# DIO_buffer.net
KiCad netlist of a schematic drawn in Altium Designer
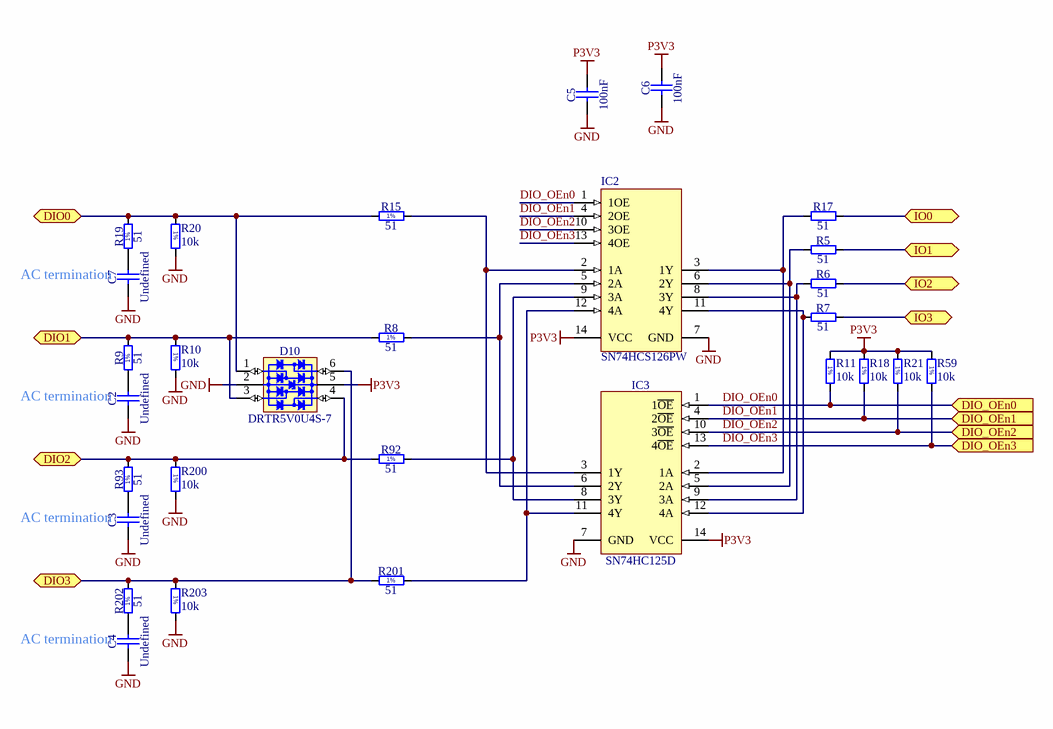
[diagram p0: DIO_buffer.schdoc]

(export (version "E")
  (design (tool "Eeschema 10.0.6"))
  (components
    (comp (ref "C2")
      (value "Undefined")
      (footprint "CAPC1608X90N")
      (description "Non-polarised capacitor")
      (fields (field (name "PART NUMBER") "CC0603_NO-VALUE") (field (name "AUTHOR") "CERN DEM MR"))
      (libsource (lib "Capacitors") (part "Capacitor - non polarized"))
    )
    (comp (ref "C3")
      (value "Undefined")
      (footprint "CAPC1608X90N")
      (description "Non-polarised capacitor")
      (fields (field (name "PART NUMBER") "CC0603_NO-VALUE") (field (name "AUTHOR") "CERN DEM MR"))
      (libsource (lib "Capacitors") (part "Capacitor - non polarized"))
    )
    (comp (ref "C4")
      (value "Undefined")
      (footprint "CAPC1608X90N")
      (description "Non-polarised capacitor")
      (fields (field (name "PART NUMBER") "CC0603_NO-VALUE") (field (name "AUTHOR") "CERN DEM MR"))
      (libsource (lib "Capacitors") (part "Capacitor - non polarized"))
    )
    (comp (ref "C5")
      (value "100nF")
      (footprint "CAPC1005X55N")
      (description "Non-polarised capacitor")
      (fields
        (field (name "PART NUMBER") "CC0402_100NF_16V_10%_X5R")
        (field (name "VOLTAGE") "16V")
        (field (name "AUTHOR") "CERN DEM JLC")
      )
      (libsource (lib "Capacitors") (part "Capacitor - non polarized"))
    )
    (comp (ref "C6")
      (value "100nF")
      (footprint "CAPC1005X55N")
      (description "Non-polarised capacitor")
      (fields
        (field (name "PART NUMBER") "CC0402_100NF_16V_10%_X5R")
        (field (name "VOLTAGE") "16V")
        (field (name "AUTHOR") "CERN DEM JLC")
      )
      (libsource (lib "Capacitors") (part "Capacitor - non polarized"))
    )
    (comp (ref "C7")
      (value "Undefined")
      (footprint "CAPC1608X90N")
      (description "Non-polarised capacitor")
      (fields (field (name "PART NUMBER") "CC0603_NO-VALUE") (field (name "AUTHOR") "CERN DEM MR"))
      (libsource (lib "Capacitors") (part "Capacitor - non polarized"))
    )
    (comp (ref "D10")
      (value "DRTR5V0U4S-7")
      (footprint "SOT65P210X110-6N")
      (description "Integrated Quad Ultra-Low Capacitance ESD Protection")
      (fields (field (name "MANUFACTURER") "DIODES") (field (name "AUTHOR") "GK"))
      (libsource (lib "Diodes") (part "D_TVS_DRTR5V0U4S-7"))
    )
    (comp (ref "IC2")
      (value "SN74HCS126PW")
      (footprint "SOP65P640X120-14N")
      (description "Quadruple Bus Buffer with 3-State Outputs")
      (fields (field (name "MANUFACTURER") "TEXAS INSTRUMENTS") (field (name "AUTHOR") "CERN DEM BC"))
      (libsource (lib "ICs And Semiconductors") (part "74126"))
    )
    (comp (ref "IC3")
      (value "SN74HC125D")
      (footprint "SOIC127P600X175-14N")
      (description "Quadruple Bus Buffer with 3-State Outputs")
      (fields (field (name "MANUFACTURER") "TEXAS INSTRUMENTS") (field (name "AUTHOR") "CERN DEM JLC"))
      (libsource (lib "ICs And Semiconductors") (part "74125"))
    )
    (comp (ref "R5")
      (value "51")
      (footprint "RESC1005X40N")
      (description "Resistor - 1%")
      (fields
        (field (name "PART NUMBER") "R0402_51R_1%_0.0625W_100PPM")
        (field (name "POWER") "0.0625W")
        (field (name "AUTHOR") "CERN DEM JLC")
      )
      (libsource (lib "Resistors") (part "Resistor - 1%"))
    )
    (comp (ref "R6")
      (value "51")
      (footprint "RESC1005X40N")
      (description "Resistor - 1%")
      (fields
        (field (name "PART NUMBER") "R0402_51R_1%_0.0625W_100PPM")
        (field (name "POWER") "0.0625W")
        (field (name "AUTHOR") "CERN DEM JLC")
      )
      (libsource (lib "Resistors") (part "Resistor - 1%"))
    )
    (comp (ref "R7")
      (value "51")
      (footprint "RESC1005X40N")
      (description "Resistor - 1%")
      (fields
        (field (name "PART NUMBER") "R0402_51R_1%_0.0625W_100PPM")
        (field (name "POWER") "0.0625W")
        (field (name "AUTHOR") "CERN DEM JLC")
      )
      (libsource (lib "Resistors") (part "Resistor - 1%"))
    )
    (comp (ref "R8")
      (value "51")
      (footprint "RESC1005X40N")
      (description "Resistor - 1%")
      (fields
        (field (name "PART NUMBER") "R0402_51R_1%_0.0625W_100PPM")
        (field (name "POWER") "0.0625W")
        (field (name "AUTHOR") "CERN DEM JLC")
      )
      (libsource (lib "Resistors") (part "Resistor - 1%"))
    )
    (comp (ref "R9")
      (value "51")
      (footprint "RESC1005X40N")
      (description "Resistor - 1%")
      (fields
        (field (name "PART NUMBER") "R0402_51R_1%_0.0625W_100PPM")
        (field (name "POWER") "0.0625W")
        (field (name "AUTHOR") "CERN DEM JLC")
      )
      (libsource (lib "Resistors") (part "Resistor - 1%"))
    )
    (comp (ref "R10")
      (value "10k")
      (footprint "RESC1005X40N")
      (description "Resistor - 1%")
      (fields
        (field (name "PART NUMBER") "R0402_10K_1%_0.0625W_100PPM")
        (field (name "POWER") "0.0625W")
        (field (name "AUTHOR") "CERN DEM JLC")
      )
      (libsource (lib "Resistors") (part "Resistor - 1%"))
    )
    (comp (ref "R11")
      (value "10k")
      (footprint "RESC1005X40N")
      (description "Resistor - 1%")
      (fields
        (field (name "PART NUMBER") "R0402_10K_1%_0.0625W_100PPM")
        (field (name "POWER") "0.0625W")
        (field (name "AUTHOR") "CERN DEM JLC")
      )
      (libsource (lib "Resistors") (part "Resistor - 1%"))
    )
    (comp (ref "R15")
      (value "51")
      (footprint "RESC1005X40N")
      (description "Resistor - 1%")
      (fields
        (field (name "PART NUMBER") "R0402_51R_1%_0.0625W_100PPM")
        (field (name "POWER") "0.0625W")
        (field (name "AUTHOR") "CERN DEM JLC")
      )
      (libsource (lib "Resistors") (part "Resistor - 1%"))
    )
    (comp (ref "R17")
      (value "51")
      (footprint "RESC1005X40N")
      (description "Resistor - 1%")
      (fields
        (field (name "PART NUMBER") "R0402_51R_1%_0.0625W_100PPM")
        (field (name "POWER") "0.0625W")
        (field (name "AUTHOR") "CERN DEM JLC")
      )
      (libsource (lib "Resistors") (part "Resistor - 1%"))
    )
    (comp (ref "R18")
      (value "10k")
      (footprint "RESC1005X40N")
      (description "Resistor - 1%")
      (fields
        (field (name "PART NUMBER") "R0402_10K_1%_0.0625W_100PPM")
        (field (name "POWER") "0.0625W")
        (field (name "AUTHOR") "CERN DEM JLC")
      )
      (libsource (lib "Resistors") (part "Resistor - 1%"))
    )
    (comp (ref "R19")
      (value "51")
      (footprint "RESC1005X40N")
      (description "Resistor - 1%")
      (fields
        (field (name "PART NUMBER") "R0402_51R_1%_0.0625W_100PPM")
        (field (name "POWER") "0.0625W")
        (field (name "AUTHOR") "CERN DEM JLC")
      )
      (libsource (lib "Resistors") (part "Resistor - 1%"))
    )
    (comp (ref "R20")
      (value "10k")
      (footprint "RESC1005X40N")
      (description "Resistor - 1%")
      (fields
        (field (name "PART NUMBER") "R0402_10K_1%_0.0625W_100PPM")
        (field (name "POWER") "0.0625W")
        (field (name "AUTHOR") "CERN DEM JLC")
      )
      (libsource (lib "Resistors") (part "Resistor - 1%"))
    )
    (comp (ref "R21")
      (value "10k")
      (footprint "RESC1005X40N")
      (description "Resistor - 1%")
      (fields
        (field (name "PART NUMBER") "R0402_10K_1%_0.0625W_100PPM")
        (field (name "POWER") "0.0625W")
        (field (name "AUTHOR") "CERN DEM JLC")
      )
      (libsource (lib "Resistors") (part "Resistor - 1%"))
    )
    (comp (ref "R59")
      (value "10k")
      (footprint "RESC1005X40N")
      (description "Resistor - 1%")
      (fields
        (field (name "PART NUMBER") "R0402_10K_1%_0.0625W_100PPM")
        (field (name "POWER") "0.0625W")
        (field (name "AUTHOR") "CERN DEM JLC")
      )
      (libsource (lib "Resistors") (part "Resistor - 1%"))
    )
    (comp (ref "R92")
      (value "51")
      (footprint "RESC1005X40N")
      (description "Resistor - 1%")
      (fields
        (field (name "PART NUMBER") "R0402_51R_1%_0.0625W_100PPM")
        (field (name "POWER") "0.0625W")
        (field (name "AUTHOR") "CERN DEM JLC")
      )
      (libsource (lib "Resistors") (part "Resistor - 1%"))
    )
    (comp (ref "R93")
      (value "51")
      (footprint "RESC1005X40N")
      (description "Resistor - 1%")
      (fields
        (field (name "PART NUMBER") "R0402_51R_1%_0.0625W_100PPM")
        (field (name "POWER") "0.0625W")
        (field (name "AUTHOR") "CERN DEM JLC")
      )
      (libsource (lib "Resistors") (part "Resistor - 1%"))
    )
    (comp (ref "R200")
      (value "10k")
      (footprint "RESC1005X40N")
      (description "Resistor - 1%")
      (fields
        (field (name "PART NUMBER") "R0402_10K_1%_0.0625W_100PPM")
        (field (name "POWER") "0.0625W")
        (field (name "AUTHOR") "CERN DEM JLC")
      )
      (libsource (lib "Resistors") (part "Resistor - 1%"))
    )
    (comp (ref "R201")
      (value "51")
      (footprint "RESC1005X40N")
      (description "Resistor - 1%")
      (fields
        (field (name "PART NUMBER") "R0402_51R_1%_0.0625W_100PPM")
        (field (name "POWER") "0.0625W")
        (field (name "AUTHOR") "CERN DEM JLC")
      )
      (libsource (lib "Resistors") (part "Resistor - 1%"))
    )
    (comp (ref "R202")
      (value "51")
      (footprint "RESC1005X40N")
      (description "Resistor - 1%")
      (fields
        (field (name "PART NUMBER") "R0402_51R_1%_0.0625W_100PPM")
        (field (name "POWER") "0.0625W")
        (field (name "AUTHOR") "CERN DEM JLC")
      )
      (libsource (lib "Resistors") (part "Resistor - 1%"))
    )
    (comp (ref "R203")
      (value "10k")
      (footprint "RESC1005X40N")
      (description "Resistor - 1%")
      (fields
        (field (name "PART NUMBER") "R0402_10K_1%_0.0625W_100PPM")
        (field (name "POWER") "0.0625W")
        (field (name "AUTHOR") "CERN DEM JLC")
      )
      (libsource (lib "Resistors") (part "Resistor - 1%"))
    )
  )
  (nets
    (net (code "1") (name "/DIO0") (class "Default")
      (node (ref "D10") (pin "1") (pinfunction "I/O1_1") (pintype "bidirectional"))
      (node (ref "R15") (pin "1") (pinfunction "1_1") (pintype "passive"))
      (node (ref "R19") (pin "2") (pinfunction "2_2") (pintype "passive"))
      (node (ref "R20") (pin "1") (pinfunction "1_1") (pintype "passive"))
    )
    (net (code "2") (name "/DIO1") (class "Default")
      (node (ref "D10") (pin "3") (pinfunction "I/O2_3") (pintype "bidirectional"))
      (node (ref "R10") (pin "1") (pinfunction "1_1") (pintype "passive"))
      (node (ref "R8") (pin "1") (pinfunction "1_1") (pintype "passive"))
      (node (ref "R9") (pin "2") (pinfunction "2_2") (pintype "passive"))
    )
    (net (code "3") (name "/DIO2") (class "Default")
      (node (ref "D10") (pin "4") (pinfunction "I/O3_4") (pintype "bidirectional"))
      (node (ref "R200") (pin "1") (pinfunction "1_1") (pintype "passive"))
      (node (ref "R92") (pin "1") (pinfunction "1_1") (pintype "passive"))
      (node (ref "R93") (pin "2") (pinfunction "2_2") (pintype "passive"))
    )
    (net (code "4") (name "/DIO3") (class "Default")
      (node (ref "D10") (pin "6") (pinfunction "I/O4_6") (pintype "bidirectional"))
      (node (ref "R201") (pin "1") (pinfunction "1_1") (pintype "passive"))
      (node (ref "R202") (pin "2") (pinfunction "2_2") (pintype "passive"))
      (node (ref "R203") (pin "1") (pinfunction "1_1") (pintype "passive"))
    )
    (net (code "5") (name "/DIO_OEn0") (class "Default")
      (node (ref "IC2") (pin "1") (pinfunction "1OE_1") (pintype "input"))
      (node (ref "IC3") (pin "1") (pinfunction "1~{OE}_1") (pintype "input"))
      (node (ref "R11") (pin "2") (pinfunction "2_2") (pintype "passive"))
    )
    (net (code "6") (name "/DIO_OEn1") (class "Default")
      (node (ref "IC2") (pin "4") (pinfunction "2OE_4") (pintype "input"))
      (node (ref "IC3") (pin "4") (pinfunction "2~{OE}_4") (pintype "input"))
      (node (ref "R18") (pin "2") (pinfunction "2_2") (pintype "passive"))
    )
    (net (code "7") (name "/DIO_OEn2") (class "Default")
      (node (ref "IC2") (pin "10") (pinfunction "3OE_10") (pintype "input"))
      (node (ref "IC3") (pin "10") (pinfunction "3~{OE}_10") (pintype "input"))
      (node (ref "R21") (pin "2") (pinfunction "2_2") (pintype "passive"))
    )
    (net (code "8") (name "/DIO_OEn3") (class "Default")
      (node (ref "IC2") (pin "13") (pinfunction "4OE_13") (pintype "input"))
      (node (ref "IC3") (pin "13") (pinfunction "4~{OE}_13") (pintype "input"))
      (node (ref "R59") (pin "2") (pinfunction "2_2") (pintype "passive"))
    )
    (net (code "9") (name "/IO0") (class "Default")
      (node (ref "R17") (pin "2") (pinfunction "2_2") (pintype "passive"))
    )
    (net (code "10") (name "/IO1") (class "Default")
      (node (ref "R5") (pin "2") (pinfunction "2_2") (pintype "passive"))
    )
    (net (code "11") (name "/IO2") (class "Default")
      (node (ref "R6") (pin "2") (pinfunction "2_2") (pintype "passive"))
    )
    (net (code "12") (name "/IO3") (class "Default")
      (node (ref "R7") (pin "2") (pinfunction "2_2") (pintype "passive"))
    )
    (net (code "13") (name "GND") (class "Default")
      (node (ref "C2") (pin "1") (pinfunction "1_1") (pintype "passive"))
      (node (ref "C3") (pin "1") (pinfunction "1_1") (pintype "passive"))
      (node (ref "C4") (pin "1") (pinfunction "1_1") (pintype "passive"))
      (node (ref "C5") (pin "1") (pinfunction "1_1") (pintype "passive"))
      (node (ref "C6") (pin "1") (pinfunction "1_1") (pintype "passive"))
      (node (ref "C7") (pin "1") (pinfunction "1_1") (pintype "passive"))
      (node (ref "D10") (pin "2") (pinfunction "GND_2") (pintype "power_in"))
      (node (ref "IC2") (pin "7") (pinfunction "GND_7") (pintype "power_in"))
      (node (ref "IC3") (pin "7") (pinfunction "GND_7") (pintype "power_in"))
      (node (ref "R10") (pin "2") (pinfunction "2_2") (pintype "passive"))
      (node (ref "R20") (pin "2") (pinfunction "2_2") (pintype "passive"))
      (node (ref "R200") (pin "2") (pinfunction "2_2") (pintype "passive"))
      (node (ref "R203") (pin "2") (pinfunction "2_2") (pintype "passive"))
    )
    (net (code "14") (name "Net-(C2-Pad2)") (class "Default")
      (node (ref "C2") (pin "2") (pinfunction "2_2") (pintype "passive"))
      (node (ref "R9") (pin "1") (pinfunction "1_1") (pintype "passive"))
    )
    (net (code "15") (name "Net-(C3-Pad2)") (class "Default")
      (node (ref "C3") (pin "2") (pinfunction "2_2") (pintype "passive"))
      (node (ref "R93") (pin "1") (pinfunction "1_1") (pintype "passive"))
    )
    (net (code "16") (name "Net-(C4-Pad2)") (class "Default")
      (node (ref "C4") (pin "2") (pinfunction "2_2") (pintype "passive"))
      (node (ref "R202") (pin "1") (pinfunction "1_1") (pintype "passive"))
    )
    (net (code "17") (name "Net-(C7-Pad2)") (class "Default")
      (node (ref "C7") (pin "2") (pinfunction "2_2") (pintype "passive"))
      (node (ref "R19") (pin "1") (pinfunction "1_1") (pintype "passive"))
    )
    (net (code "18") (name "Net-(IC2-1A)") (class "Default")
      (node (ref "IC2") (pin "2") (pinfunction "1A_2") (pintype "input"))
      (node (ref "IC3") (pin "3") (pinfunction "1Y_3") (pintype "tri_state"))
      (node (ref "R15") (pin "2") (pinfunction "2_2") (pintype "passive"))
    )
    (net (code "19") (name "Net-(IC2-1Y)") (class "Default")
      (node (ref "IC2") (pin "3") (pinfunction "1Y_3") (pintype "tri_state"))
      (node (ref "IC3") (pin "2") (pinfunction "1A_2") (pintype "input"))
      (node (ref "R17") (pin "1") (pinfunction "1_1") (pintype "passive"))
    )
    (net (code "20") (name "Net-(IC2-2A)") (class "Default")
      (node (ref "IC2") (pin "5") (pinfunction "2A_5") (pintype "input"))
      (node (ref "IC3") (pin "6") (pinfunction "2Y_6") (pintype "tri_state"))
      (node (ref "R8") (pin "2") (pinfunction "2_2") (pintype "passive"))
    )
    (net (code "21") (name "Net-(IC2-2Y)") (class "Default")
      (node (ref "IC2") (pin "6") (pinfunction "2Y_6") (pintype "tri_state"))
      (node (ref "IC3") (pin "5") (pinfunction "2A_5") (pintype "input"))
      (node (ref "R5") (pin "1") (pinfunction "1_1") (pintype "passive"))
    )
    (net (code "22") (name "Net-(IC2-3A)") (class "Default")
      (node (ref "IC2") (pin "9") (pinfunction "3A_9") (pintype "input"))
      (node (ref "IC3") (pin "8") (pinfunction "3Y_8") (pintype "tri_state"))
      (node (ref "R92") (pin "2") (pinfunction "2_2") (pintype "passive"))
    )
    (net (code "23") (name "Net-(IC2-3Y)") (class "Default")
      (node (ref "IC2") (pin "8") (pinfunction "3Y_8") (pintype "tri_state"))
      (node (ref "IC3") (pin "9") (pinfunction "3A_9") (pintype "input"))
      (node (ref "R6") (pin "1") (pinfunction "1_1") (pintype "passive"))
    )
    (net (code "24") (name "Net-(IC2-4A)") (class "Default")
      (node (ref "IC2") (pin "12") (pinfunction "4A_12") (pintype "input"))
      (node (ref "IC3") (pin "11") (pinfunction "4Y_11") (pintype "tri_state"))
      (node (ref "R201") (pin "2") (pinfunction "2_2") (pintype "passive"))
    )
    (net (code "25") (name "Net-(IC2-4Y)") (class "Default")
      (node (ref "IC2") (pin "11") (pinfunction "4Y_11") (pintype "tri_state"))
      (node (ref "IC3") (pin "12") (pinfunction "4A_12") (pintype "input"))
      (node (ref "R7") (pin "1") (pinfunction "1_1") (pintype "passive"))
    )
    (net (code "26") (name "P3V3") (class "Default")
      (node (ref "C5") (pin "2") (pinfunction "2_2") (pintype "passive"))
      (node (ref "C6") (pin "2") (pinfunction "2_2") (pintype "passive"))
      (node (ref "D10") (pin "5") (pinfunction "VBUS_5") (pintype "power_in"))
      (node (ref "IC2") (pin "14") (pinfunction "VCC_14") (pintype "power_in"))
      (node (ref "IC3") (pin "14") (pinfunction "VCC_14") (pintype "power_in"))
      (node (ref "R11") (pin "1") (pinfunction "1_1") (pintype "passive"))
      (node (ref "R18") (pin "1") (pinfunction "1_1") (pintype "passive"))
      (node (ref "R21") (pin "1") (pinfunction "1_1") (pintype "passive"))
      (node (ref "R59") (pin "1") (pinfunction "1_1") (pintype "passive"))
    )
  )
)
